# isolator.net
KiCad netlist of a schematic drawn in Altium Designer
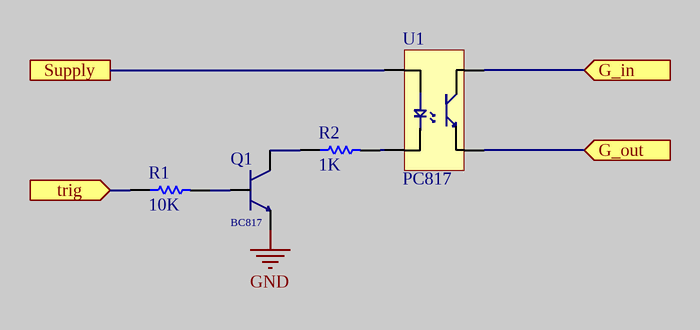
[diagram p0: isolator.SchDoc]

(export (version "E")
  (design (tool "Eeschema 10.0.6"))
  (components
    (comp (ref "Q1")
      (value "NPN transistor")
      (footprint "NPN")
      (description "45 V, 0.5 A")
      (fields (field (name "TRANSISTOR") "BC817"))
      (libsource (lib "eLIB") (part "BC817"))
    )
    (comp (ref "R1")
      (value "10K")
      (footprint "RESC0603")
      (description "0603,0.1W")
      (fields (field (name "PUBLISHER") "Altium Limited"))
      (libsource (lib "eLIB") (part "Resistor"))
    )
    (comp (ref "R2")
      (value "1K")
      (footprint "RESC0603")
      (description "0603,0.1W")
      (fields (field (name "PUBLISHER") "Altium Limited"))
      (libsource (lib "eLIB") (part "Resistor"))
    )
    (comp (ref "U1")
      (value "PC817")
      (footprint "PC817")
      (description "PC817 optocoupler")
      (libsource (lib "eLIB") (part "PC817"))
    )
  )
  (nets
    (net (code "1") (name "/G_in") (class "Default")
      (node (ref "U1") (pin "4") (pinfunction "4_4") (pintype "passive"))
    )
    (net (code "2") (name "/G_out") (class "Default")
      (node (ref "U1") (pin "3") (pinfunction "3_3") (pintype "passive"))
    )
    (net (code "3") (name "/Supply") (class "Default")
      (node (ref "U1") (pin "1") (pinfunction "1_1") (pintype "passive"))
    )
    (net (code "4") (name "/trig") (class "Default")
      (node (ref "R1") (pin "1") (pinfunction "1_1") (pintype "passive"))
    )
    (net (code "5") (name "GND") (class "Default")
      (node (ref "Q1") (pin "2") (pinfunction "E_2") (pintype "passive"))
    )
    (net (code "6") (name "Net-(Q1-B)") (class "Default")
      (node (ref "Q1") (pin "1") (pinfunction "B_1") (pintype "passive"))
      (node (ref "R1") (pin "2") (pinfunction "2_2") (pintype "passive"))
    )
    (net (code "7") (name "Net-(Q1-C)") (class "Default")
      (node (ref "Q1") (pin "3") (pinfunction "C_3") (pintype "passive"))
      (node (ref "R2") (pin "1") (pinfunction "1_1") (pintype "passive"))
    )
    (net (code "8") (name "Net-(R2-Pad2)") (class "Default")
      (node (ref "R2") (pin "2") (pinfunction "2_2") (pintype "passive"))
      (node (ref "U1") (pin "2") (pinfunction "2_2") (pintype "passive"))
    )
  )
)
